# l_meter.net
KiCad netlist of a schematic drawn in EAGLE
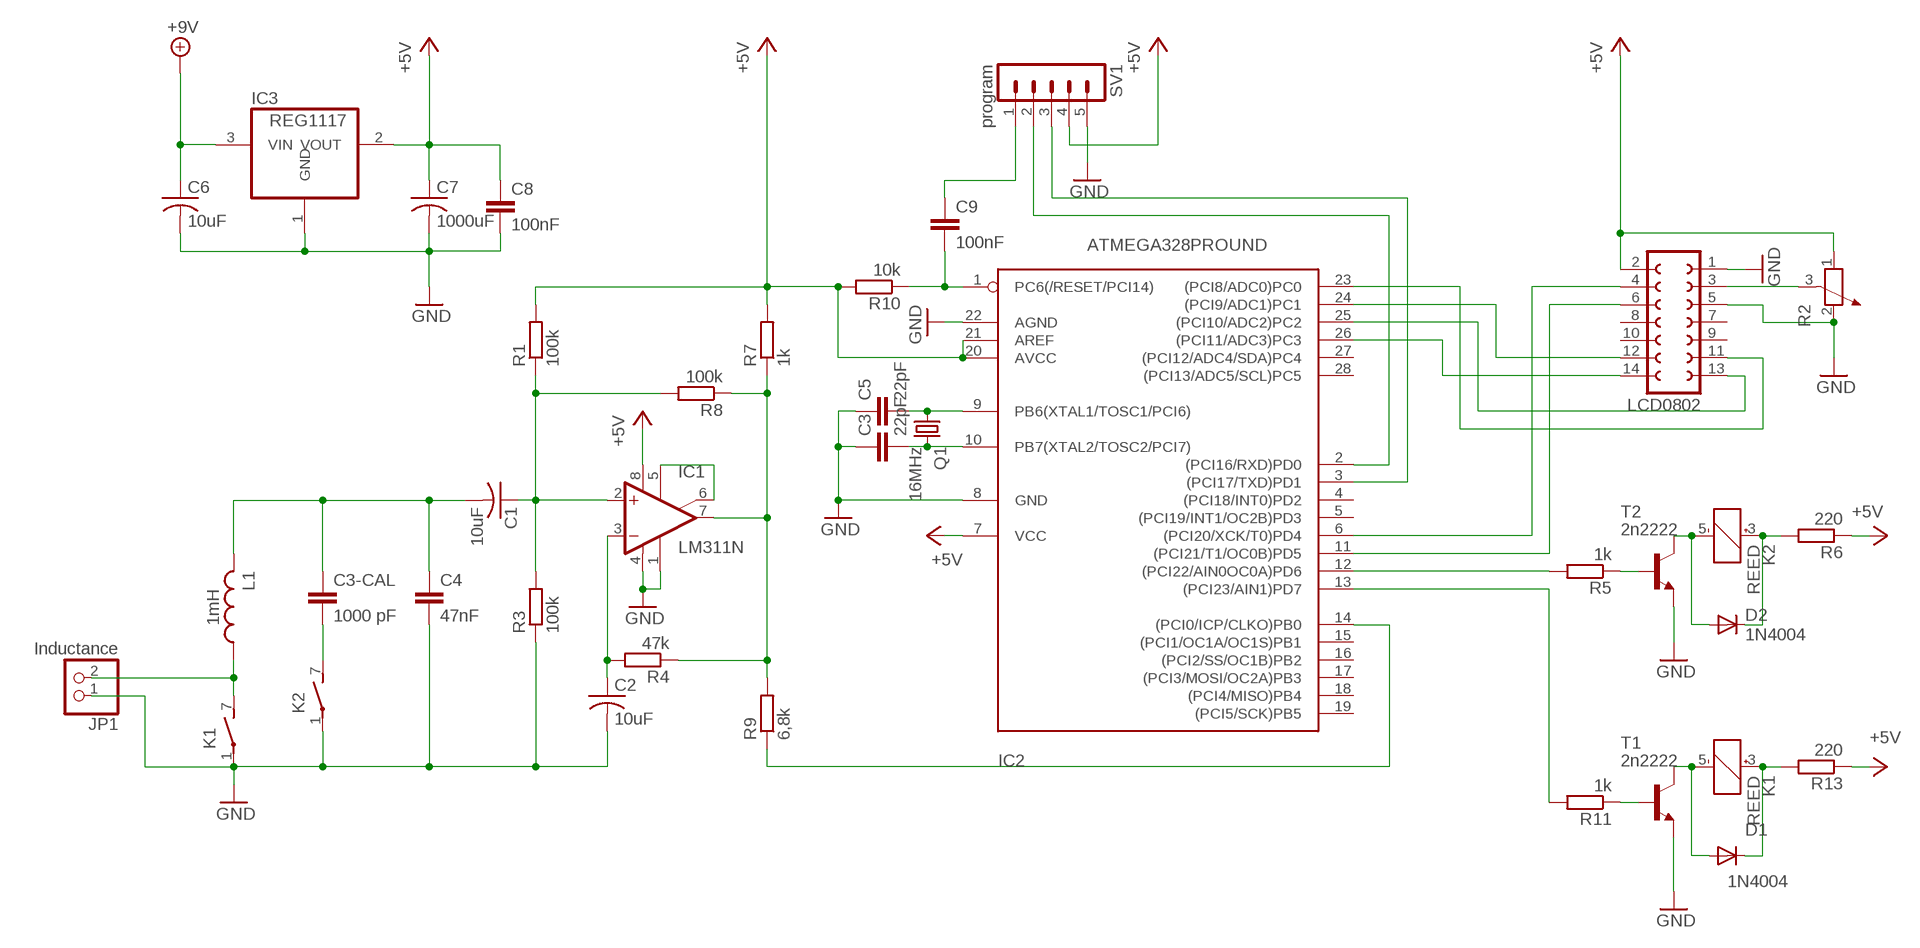
[diagram p0: schematic, sheet 1]

(export (version "E")
  (design (tool "Eeschema 10.0.6"))
  (components
    (comp (ref "C1")
      (value "10uF")
      (footprint "eagle-import:C025-024X044")
      (libsource (lib "eagle-import") (part "C-US025-024X044"))
    )
    (comp (ref "C2")
      (value "10uF")
      (footprint "eagle-import:C025-024X044")
      (libsource (lib "eagle-import") (part "C-US025-024X044"))
    )
    (comp (ref "C3")
      (value "22pF")
      (footprint "eagle-import:C2.5-3")
      (libsource (lib "eagle-import") (part "C2,5-3"))
    )
    (comp (ref "C3-CAL")
      (value "1000 pF")
      (footprint "eagle-import:C2.5-3")
      (libsource (lib "eagle-import") (part "C2,5-3"))
    )
    (comp (ref "C4")
      (value "47nF")
      (footprint "eagle-import:C2.5-3")
      (libsource (lib "eagle-import") (part "C2,5-3"))
    )
    (comp (ref "C5")
      (value "22pF")
      (footprint "eagle-import:C2.5-3")
      (libsource (lib "eagle-import") (part "C2,5-3"))
    )
    (comp (ref "C6")
      (value "10uF")
      (footprint "eagle-import:C025-024X044")
      (libsource (lib "eagle-import") (part "C-US025-024X044"))
    )
    (comp (ref "C7")
      (value "1000uF")
      (footprint "eagle-import:C025-024X044")
      (libsource (lib "eagle-import") (part "C-US025-024X044"))
    )
    (comp (ref "C8")
      (value "100nF")
      (footprint "eagle-import:C2.5-3")
      (libsource (lib "eagle-import") (part "C2,5-3"))
    )
    (comp (ref "C9")
      (value "100nF")
      (footprint "eagle-import:C2.5-3")
      (libsource (lib "eagle-import") (part "C2,5-3"))
    )
    (comp (ref "D1")
      (value "1N4004")
      (footprint "eagle-import:DO41-10")
      (libsource (lib "eagle-import") (part "1N4004"))
    )
    (comp (ref "D2")
      (value "1N4004")
      (footprint "eagle-import:DO41-10")
      (libsource (lib "eagle-import") (part "1N4004"))
    )
    (comp (ref "IC1")
      (value "LM311N")
      (footprint "eagle-import:DIL08")
      (libsource (lib "eagle-import") (part "LM311N"))
    )
    (comp (ref "IC2")
      (value "ATMEGA328PROUND")
      (footprint "eagle-import:DIL28-3-ROUND")
      (libsource (lib "eagle-import") (part "ATMEGA328PROUND"))
    )
    (comp (ref "IC3")
      (value "REG1117")
      (footprint "eagle-import:SOT223")
      (libsource (lib "eagle-import") (part "REG1117"))
    )
    (comp (ref "JP1")
      (value "Inductance")
      (footprint "eagle-import:1X02")
      (libsource (lib "eagle-import") (part "PINHD-1X2"))
    )
    (comp (ref "K1")
      (value "REED")
      (footprint "eagle-import:REED")
      (libsource (lib "eagle-import") (part "REED"))
    )
    (comp (ref "K2")
      (value "REED")
      (footprint "eagle-import:REED")
      (libsource (lib "eagle-import") (part "REED"))
    )
    (comp (ref "L1")
      (value "1mH")
      (footprint "eagle-import:RESC0805_N")
      (libsource (lib "eagle-import") (part "INDUCTOR_0805_N"))
    )
    (comp (ref "LCD0802")
      (value "FE07-2")
      (footprint "eagle-import:FE07-2")
      (libsource (lib "eagle-import") (part "FE07-2"))
    )
    (comp (ref "Q1")
      (value "16MHz")
      (footprint "eagle-import:HC18U-V")
      (libsource (lib "eagle-import") (part "CRYSTALHC18U-V"))
    )
    (comp (ref "R1")
      (value "100k")
      (footprint "eagle-import:0204_7")
      (libsource (lib "eagle-import") (part "R0204/7"))
    )
    (comp (ref "R2")
      (value "POTENTIOMETER_PT_SPIN")
      (footprint "eagle-import:PT-SPIN")
      (libsource (lib "eagle-import") (part "POTENTIOMETER_PT_SPIN"))
    )
    (comp (ref "R3")
      (value "100k")
      (footprint "eagle-import:0204_7")
      (libsource (lib "eagle-import") (part "R0204/7"))
    )
    (comp (ref "R4")
      (value "47k")
      (footprint "eagle-import:0204_7")
      (libsource (lib "eagle-import") (part "R0204/7"))
    )
    (comp (ref "R5")
      (value "1k")
      (footprint "eagle-import:0204_7")
      (libsource (lib "eagle-import") (part "R0204/7"))
    )
    (comp (ref "R6")
      (value "220")
      (footprint "eagle-import:0204_7")
      (libsource (lib "eagle-import") (part "R0204/7"))
    )
    (comp (ref "R7")
      (value "1k")
      (footprint "eagle-import:0204_7")
      (libsource (lib "eagle-import") (part "R0204/7"))
    )
    (comp (ref "R8")
      (value "100k")
      (footprint "eagle-import:0204_7")
      (libsource (lib "eagle-import") (part "R0204/7"))
    )
    (comp (ref "R9")
      (value "6,8k")
      (footprint "eagle-import:0204_7")
      (libsource (lib "eagle-import") (part "R0204/7"))
    )
    (comp (ref "R10")
      (value "10k")
      (footprint "eagle-import:0204_7")
      (libsource (lib "eagle-import") (part "R0204/7"))
    )
    (comp (ref "R11")
      (value "1k")
      (footprint "eagle-import:0204_7")
      (libsource (lib "eagle-import") (part "R0204/7"))
    )
    (comp (ref "R13")
      (value "220")
      (footprint "eagle-import:0204_7")
      (libsource (lib "eagle-import") (part "R0204/7"))
    )
    (comp (ref "SV1")
      (value "program")
      (footprint "eagle-import:MA05-1")
      (libsource (lib "eagle-import") (part "MA05-1"))
    )
    (comp (ref "T1")
      (value "2n2222")
      (footprint "eagle-import:TO92-EBC")
      (libsource (lib "eagle-import") (part "-NPN-TO92-EBC2N2222"))
    )
    (comp (ref "T2")
      (value "2n2222")
      (footprint "eagle-import:TO92-EBC")
      (libsource (lib "eagle-import") (part "-NPN-TO92-EBC2N2222"))
    )
  )
  (nets
    (net (code "1") (name "+5V") (class "Default")
      (node (ref "C7") (pin "1") (pinfunction "1_1") (pintype "passive"))
      (node (ref "C8") (pin "1") (pinfunction "1_1") (pintype "passive"))
      (node (ref "IC1") (pin "8") (pinfunction "V+_8") (pintype "power_in"))
      (node (ref "IC2") (pin "20") (pinfunction "AVCC_20") (pintype "bidirectional"))
      (node (ref "IC2") (pin "21") (pinfunction "AREF_21") (pintype "bidirectional"))
      (node (ref "IC2") (pin "7") (pinfunction "VCC_7") (pintype "bidirectional"))
      (node (ref "IC3") (pin "2") (pinfunction "VOUT_2") (pintype "output"))
      (node (ref "LCD0802") (pin "2") (pinfunction "2_2") (pintype "passive"))
      (node (ref "R1") (pin "2") (pinfunction "2_2") (pintype "passive"))
      (node (ref "R10") (pin "2") (pinfunction "2_2") (pintype "passive"))
      (node (ref "R13") (pin "1") (pinfunction "1_1") (pintype "passive"))
      (node (ref "R2") (pin "1") (pinfunction "1_1") (pintype "passive"))
      (node (ref "R6") (pin "1") (pinfunction "1_1") (pintype "passive"))
      (node (ref "R7") (pin "2") (pinfunction "2_2") (pintype "passive"))
      (node (ref "SV1") (pin "4") (pinfunction "4_4") (pintype "passive"))
    )
    (net (code "2") (name "+9V") (class "Default")
      (node (ref "C6") (pin "1") (pinfunction "1_1") (pintype "passive"))
      (node (ref "IC3") (pin "3") (pinfunction "VIN_3") (pintype "input"))
    )
    (net (code "3") (name "GND") (class "Default")
      (node (ref "C2") (pin "2") (pinfunction "2_2") (pintype "passive"))
      (node (ref "C3") (pin "1") (pinfunction "1_1") (pintype "passive"))
      (node (ref "C4") (pin "2") (pinfunction "2_2") (pintype "passive"))
      (node (ref "C5") (pin "1") (pinfunction "1_1") (pintype "passive"))
      (node (ref "C6") (pin "2") (pinfunction "2_2") (pintype "passive"))
      (node (ref "C7") (pin "2") (pinfunction "2_2") (pintype "passive"))
      (node (ref "C8") (pin "2") (pinfunction "2_2") (pintype "passive"))
      (node (ref "IC1") (pin "1") (pinfunction "GND_1") (pintype "passive"))
      (node (ref "IC1") (pin "4") (pinfunction "V-_4") (pintype "power_in"))
      (node (ref "IC2") (pin "22") (pinfunction "AGND_22") (pintype "bidirectional"))
      (node (ref "IC2") (pin "8") (pinfunction "GND_8") (pintype "bidirectional"))
      (node (ref "IC3") (pin "1") (pinfunction "GND_1") (pintype "power_in"))
      (node (ref "JP1") (pin "1") (pinfunction "1_1") (pintype "passive"))
      (node (ref "K1") (pin "1") (pinfunction "P_1") (pintype "passive"))
      (node (ref "K2") (pin "1") (pinfunction "P_1") (pintype "passive"))
      (node (ref "LCD0802") (pin "1") (pinfunction "1_1") (pintype "passive"))
      (node (ref "LCD0802") (pin "5") (pinfunction "5_5") (pintype "passive"))
      (node (ref "R2") (pin "2") (pinfunction "2_2") (pintype "passive"))
      (node (ref "R3") (pin "1") (pinfunction "1_1") (pintype "passive"))
      (node (ref "SV1") (pin "5") (pinfunction "5_5") (pintype "passive"))
      (node (ref "T1") (pin "E") (pinfunction "E_E") (pintype "passive"))
      (node (ref "T2") (pin "E") (pinfunction "E_E") (pintype "passive"))
    )
    (net (code "4") (name "Net-(C1-Pad2)") (class "Default")
      (node (ref "C1") (pin "2") (pinfunction "2_2") (pintype "passive"))
      (node (ref "C3-CAL") (pin "1") (pinfunction "1_1") (pintype "passive"))
      (node (ref "C4") (pin "1") (pinfunction "1_1") (pintype "passive"))
      (node (ref "L1") (pin "2") (pinfunction "2_2") (pintype "passive"))
    )
    (net (code "5") (name "Net-(C9-Pad1)") (class "Default")
      (node (ref "C9") (pin "1") (pinfunction "1_1") (pintype "passive"))
      (node (ref "SV1") (pin "1") (pinfunction "1_1") (pintype "passive"))
    )
    (net (code "6") (name "Net-(IC1-+IN)") (class "Default")
      (node (ref "C1") (pin "1") (pinfunction "1_1") (pintype "passive"))
      (node (ref "IC1") (pin "2") (pinfunction "+IN_2") (pintype "input"))
      (node (ref "R1") (pin "1") (pinfunction "1_1") (pintype "passive"))
      (node (ref "R3") (pin "2") (pinfunction "2_2") (pintype "passive"))
      (node (ref "R8") (pin "2") (pinfunction "2_2") (pintype "passive"))
    )
    (net (code "7") (name "Net-(IC1--IN)") (class "Default")
      (node (ref "C2") (pin "1") (pinfunction "1_1") (pintype "passive"))
      (node (ref "IC1") (pin "3") (pinfunction "-IN_3") (pintype "input"))
      (node (ref "R4") (pin "2") (pinfunction "2_2") (pintype "passive"))
    )
    (net (code "8") (name "Net-(IC1-ON)") (class "Default")
      (node (ref "IC1") (pin "5") (pinfunction "ON_5") (pintype "passive"))
      (node (ref "IC1") (pin "6") (pinfunction "ON/STR_6") (pintype "passive"))
    )
    (net (code "9") (name "Net-(IC1-OUT)") (class "Default")
      (node (ref "IC1") (pin "7") (pinfunction "OUT_7") (pintype "output"))
      (node (ref "R4") (pin "1") (pinfunction "1_1") (pintype "passive"))
      (node (ref "R7") (pin "1") (pinfunction "1_1") (pintype "passive"))
      (node (ref "R8") (pin "1") (pinfunction "1_1") (pintype "passive"))
      (node (ref "R9") (pin "2") (pinfunction "2_2") (pintype "passive"))
    )
    (net (code "10") (name "Net-(IC2-(PCI0{slash}ICP{slash}CLKO)PB0)") (class "Default")
      (node (ref "IC2") (pin "14") (pinfunction "(PCI0/ICP/CLKO)PB0_14") (pintype "bidirectional"))
      (node (ref "R9") (pin "1") (pinfunction "1_1") (pintype "passive"))
    )
    (net (code "11") (name "Net-(IC2-(PCI8{slash}ADC0)PC0)") (class "Default")
      (node (ref "IC2") (pin "23") (pinfunction "(PCI8/ADC0)PC0_23") (pintype "bidirectional"))
      (node (ref "LCD0802") (pin "11") (pinfunction "11_11") (pintype "passive"))
    )
    (net (code "12") (name "Net-(IC2-(PCI9{slash}ADC1)PC1)") (class "Default")
      (node (ref "IC2") (pin "24") (pinfunction "(PCI9/ADC1)PC1_24") (pintype "bidirectional"))
      (node (ref "LCD0802") (pin "12") (pinfunction "12_12") (pintype "passive"))
    )
    (net (code "13") (name "Net-(IC2-(PCI10{slash}ADC2)PC2)") (class "Default")
      (node (ref "IC2") (pin "25") (pinfunction "(PCI10/ADC2)PC2_25") (pintype "bidirectional"))
      (node (ref "LCD0802") (pin "13") (pinfunction "13_13") (pintype "passive"))
    )
    (net (code "14") (name "Net-(IC2-(PCI11{slash}ADC3)PC3)") (class "Default")
      (node (ref "IC2") (pin "26") (pinfunction "(PCI11/ADC3)PC3_26") (pintype "bidirectional"))
      (node (ref "LCD0802") (pin "14") (pinfunction "14_14") (pintype "passive"))
    )
    (net (code "15") (name "Net-(IC2-(PCI16{slash}RXD)PD0)") (class "Default")
      (node (ref "IC2") (pin "2") (pinfunction "(PCI16/RXD)PD0_2") (pintype "bidirectional"))
      (node (ref "SV1") (pin "2") (pinfunction "2_2") (pintype "passive"))
    )
    (net (code "16") (name "Net-(IC2-(PCI17{slash}TXD)PD1)") (class "Default")
      (node (ref "IC2") (pin "3") (pinfunction "(PCI17/TXD)PD1_3") (pintype "bidirectional"))
      (node (ref "SV1") (pin "3") (pinfunction "3_3") (pintype "passive"))
    )
    (net (code "17") (name "Net-(IC2-(PCI20{slash}XCK{slash}T0)PD4)") (class "Default")
      (node (ref "IC2") (pin "6") (pinfunction "(PCI20/XCK/T0)PD4_6") (pintype "bidirectional"))
      (node (ref "LCD0802") (pin "4") (pinfunction "4_4") (pintype "passive"))
    )
    (net (code "18") (name "Net-(IC2-(PCI21{slash}T1{slash}OC0B)PD5)") (class "Default")
      (node (ref "IC2") (pin "11") (pinfunction "(PCI21/T1/OC0B)PD5_11") (pintype "bidirectional"))
      (node (ref "LCD0802") (pin "6") (pinfunction "6_6") (pintype "passive"))
    )
    (net (code "19") (name "Net-(IC2-(PCI22{slash}AIN0OC0A)PD6)") (class "Default")
      (node (ref "IC2") (pin "12") (pinfunction "(PCI22/AIN0OC0A)PD6_12") (pintype "bidirectional"))
      (node (ref "R5") (pin "2") (pinfunction "2_2") (pintype "passive"))
    )
    (net (code "20") (name "Net-(IC2-(PCI23{slash}AIN1)PD7)") (class "Default")
      (node (ref "IC2") (pin "13") (pinfunction "(PCI23/AIN1)PD7_13") (pintype "bidirectional"))
      (node (ref "R11") (pin "2") (pinfunction "2_2") (pintype "passive"))
    )
    (net (code "21") (name "Net-(IC2-PB6(XTAL1{slash}TOSC1{slash}PCI6))") (class "Default")
      (node (ref "C5") (pin "2") (pinfunction "2_2") (pintype "passive"))
      (node (ref "IC2") (pin "9") (pinfunction "PB6(XTAL1/TOSC1/PCI6)_9") (pintype "bidirectional"))
      (node (ref "Q1") (pin "1") (pinfunction "1_1") (pintype "passive"))
    )
    (net (code "22") (name "Net-(IC2-PB7(XTAL2{slash}TOSC2{slash}PCI7))") (class "Default")
      (node (ref "C3") (pin "2") (pinfunction "2_2") (pintype "passive"))
      (node (ref "IC2") (pin "10") (pinfunction "PB7(XTAL2/TOSC2/PCI7)_10") (pintype "bidirectional"))
      (node (ref "Q1") (pin "2") (pinfunction "2_2") (pintype "passive"))
    )
    (net (code "23") (name "Net-(IC2-PC6({slash}RESET{slash}PCI14))") (class "Default")
      (node (ref "C9") (pin "2") (pinfunction "2_2") (pintype "passive"))
      (node (ref "IC2") (pin "1") (pinfunction "PC6(/RESET/PCI14)_1") (pintype "bidirectional"))
      (node (ref "R10") (pin "1") (pinfunction "1_1") (pintype "passive"))
    )
    (net (code "24") (name "Net-(K1A-+)") (class "Default")
      (node (ref "D1") (pin "C") (pinfunction "C_C") (pintype "passive"))
      (node (ref "K1") (pin "3") (pinfunction "+_3") (pintype "passive"))
      (node (ref "R13") (pin "2") (pinfunction "2_2") (pintype "passive"))
    )
    (net (code "25") (name "Net-(K1A--)") (class "Default")
      (node (ref "D1") (pin "A") (pinfunction "A_A") (pintype "passive"))
      (node (ref "K1") (pin "5") (pinfunction "-_5") (pintype "passive"))
      (node (ref "T1") (pin "C") (pinfunction "C_C") (pintype "passive"))
    )
    (net (code "26") (name "Net-(K1B-S)") (class "Default")
      (node (ref "JP1") (pin "2") (pinfunction "2_2") (pintype "passive"))
      (node (ref "K1") (pin "7") (pinfunction "S_7") (pintype "passive"))
      (node (ref "L1") (pin "1") (pinfunction "1_1") (pintype "passive"))
    )
    (net (code "27") (name "Net-(K2A-+)") (class "Default")
      (node (ref "D2") (pin "C") (pinfunction "C_C") (pintype "passive"))
      (node (ref "K2") (pin "3") (pinfunction "+_3") (pintype "passive"))
      (node (ref "R6") (pin "2") (pinfunction "2_2") (pintype "passive"))
    )
    (net (code "28") (name "Net-(K2A--)") (class "Default")
      (node (ref "D2") (pin "A") (pinfunction "A_A") (pintype "passive"))
      (node (ref "K2") (pin "5") (pinfunction "-_5") (pintype "passive"))
      (node (ref "T2") (pin "C") (pinfunction "C_C") (pintype "passive"))
    )
    (net (code "29") (name "Net-(K2B-S)") (class "Default")
      (node (ref "C3-CAL") (pin "2") (pinfunction "2_2") (pintype "passive"))
      (node (ref "K2") (pin "7") (pinfunction "S_7") (pintype "passive"))
    )
    (net (code "30") (name "Net-(LCD0802-Pad3)") (class "Default")
      (node (ref "LCD0802") (pin "3") (pinfunction "3_3") (pintype "passive"))
      (node (ref "R2") (pin "3") (pinfunction "3_3") (pintype "passive"))
    )
    (net (code "31") (name "Net-(R5-Pad1)") (class "Default")
      (node (ref "R5") (pin "1") (pinfunction "1_1") (pintype "passive"))
      (node (ref "T2") (pin "B") (pinfunction "B_B") (pintype "passive"))
    )
    (net (code "32") (name "Net-(R11-Pad1)") (class "Default")
      (node (ref "R11") (pin "1") (pinfunction "1_1") (pintype "passive"))
      (node (ref "T1") (pin "B") (pinfunction "B_B") (pintype "passive"))
    )
    (net (code "33") (name "unconnected-(IC2-(PCI1{slash}OC1A{slash}OC1S)PB1-Pad15)") (class "Default")
      (node (ref "IC2") (pin "15") (pinfunction "(PCI1/OC1A/OC1S)PB1_15") (pintype "bidirectional"))
    )
    (net (code "34") (name "unconnected-(IC2-(PCI2{slash}SS{slash}OC1B)PB2-Pad16)") (class "Default")
      (node (ref "IC2") (pin "16") (pinfunction "(PCI2/SS/OC1B)PB2_16") (pintype "bidirectional"))
    )
    (net (code "35") (name "unconnected-(IC2-(PCI3{slash}MOSI{slash}OC2A)PB3-Pad17)") (class "Default")
      (node (ref "IC2") (pin "17") (pinfunction "(PCI3/MOSI/OC2A)PB3_17") (pintype "bidirectional"))
    )
    (net (code "36") (name "unconnected-(IC2-(PCI4{slash}MISO)PB4-Pad18)") (class "Default")
      (node (ref "IC2") (pin "18") (pinfunction "(PCI4/MISO)PB4_18") (pintype "bidirectional"))
    )
    (net (code "37") (name "unconnected-(IC2-(PCI5{slash}SCK)PB5-Pad19)") (class "Default")
      (node (ref "IC2") (pin "19") (pinfunction "(PCI5/SCK)PB5_19") (pintype "bidirectional"))
    )
    (net (code "38") (name "unconnected-(IC2-(PCI12{slash}ADC4{slash}SDA)PC4-Pad27)") (class "Default")
      (node (ref "IC2") (pin "27") (pinfunction "(PCI12/ADC4/SDA)PC4_27") (pintype "bidirectional"))
    )
    (net (code "39") (name "unconnected-(IC2-(PCI13{slash}ADC5{slash}SCL)PC5-Pad28)") (class "Default")
      (node (ref "IC2") (pin "28") (pinfunction "(PCI13/ADC5/SCL)PC5_28") (pintype "bidirectional"))
    )
    (net (code "40") (name "unconnected-(IC2-(PCI18{slash}INT0)PD2-Pad4)") (class "Default")
      (node (ref "IC2") (pin "4") (pinfunction "(PCI18/INT0)PD2_4") (pintype "bidirectional"))
    )
    (net (code "41") (name "unconnected-(IC2-(PCI19{slash}INT1{slash}OC2B)PD3-Pad5)") (class "Default")
      (node (ref "IC2") (pin "5") (pinfunction "(PCI19/INT1/OC2B)PD3_5") (pintype "bidirectional"))
    )
    (net (code "42") (name "unconnected-(LCD0802-Pad7)") (class "Default")
      (node (ref "LCD0802") (pin "7") (pinfunction "7_7") (pintype "passive"))
    )
    (net (code "43") (name "unconnected-(LCD0802-Pad8)") (class "Default")
      (node (ref "LCD0802") (pin "8") (pinfunction "8_8") (pintype "passive"))
    )
    (net (code "44") (name "unconnected-(LCD0802-Pad9)") (class "Default")
      (node (ref "LCD0802") (pin "9") (pinfunction "9_9") (pintype "passive"))
    )
    (net (code "45") (name "unconnected-(LCD0802-Pad10)") (class "Default")
      (node (ref "LCD0802") (pin "10") (pinfunction "10_10") (pintype "passive"))
    )
  )
)
